# Group_1-1_PP.net
KiCad netlist of a schematic drawn in EAGLE
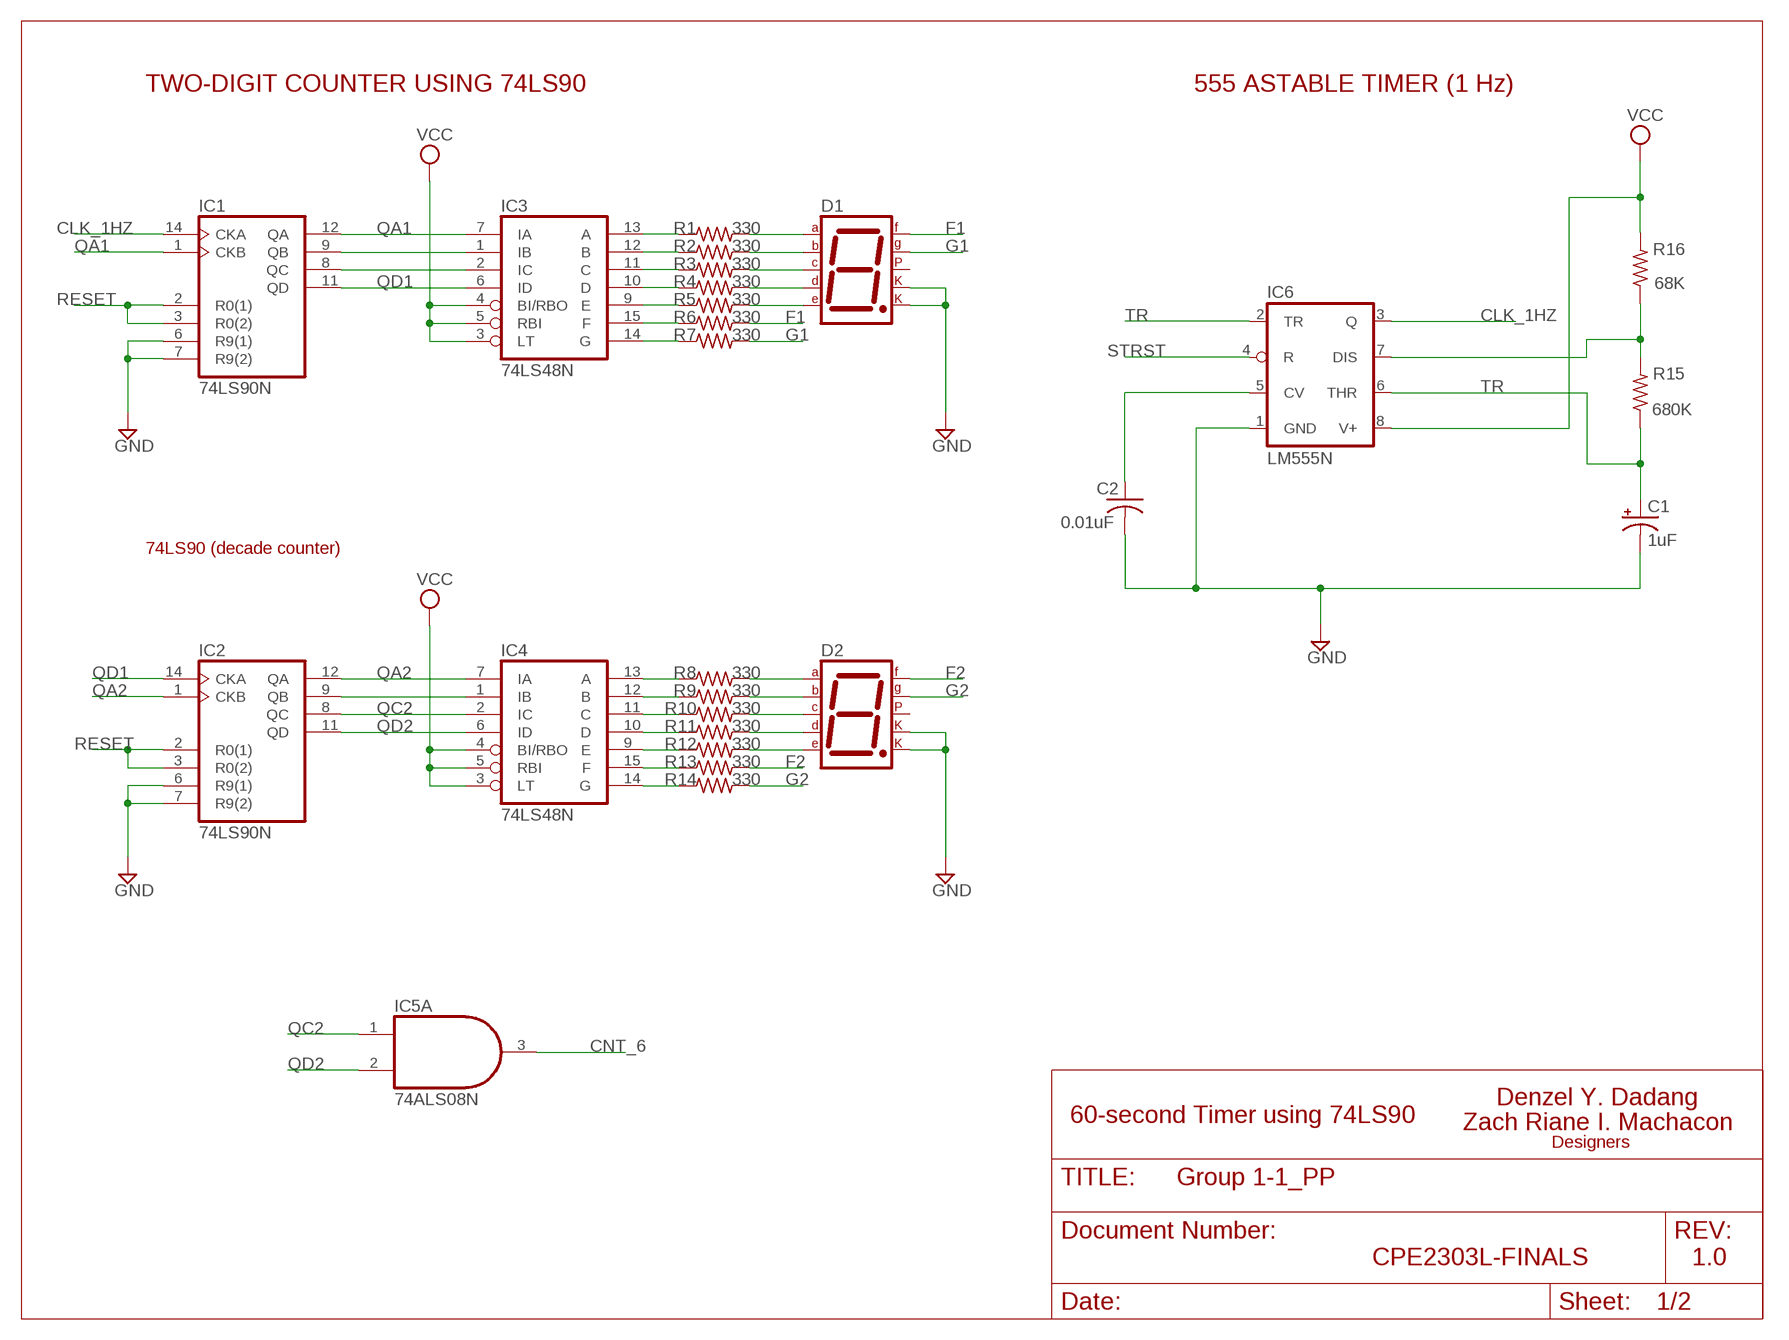
[diagram p0: schematic, sheet 1]
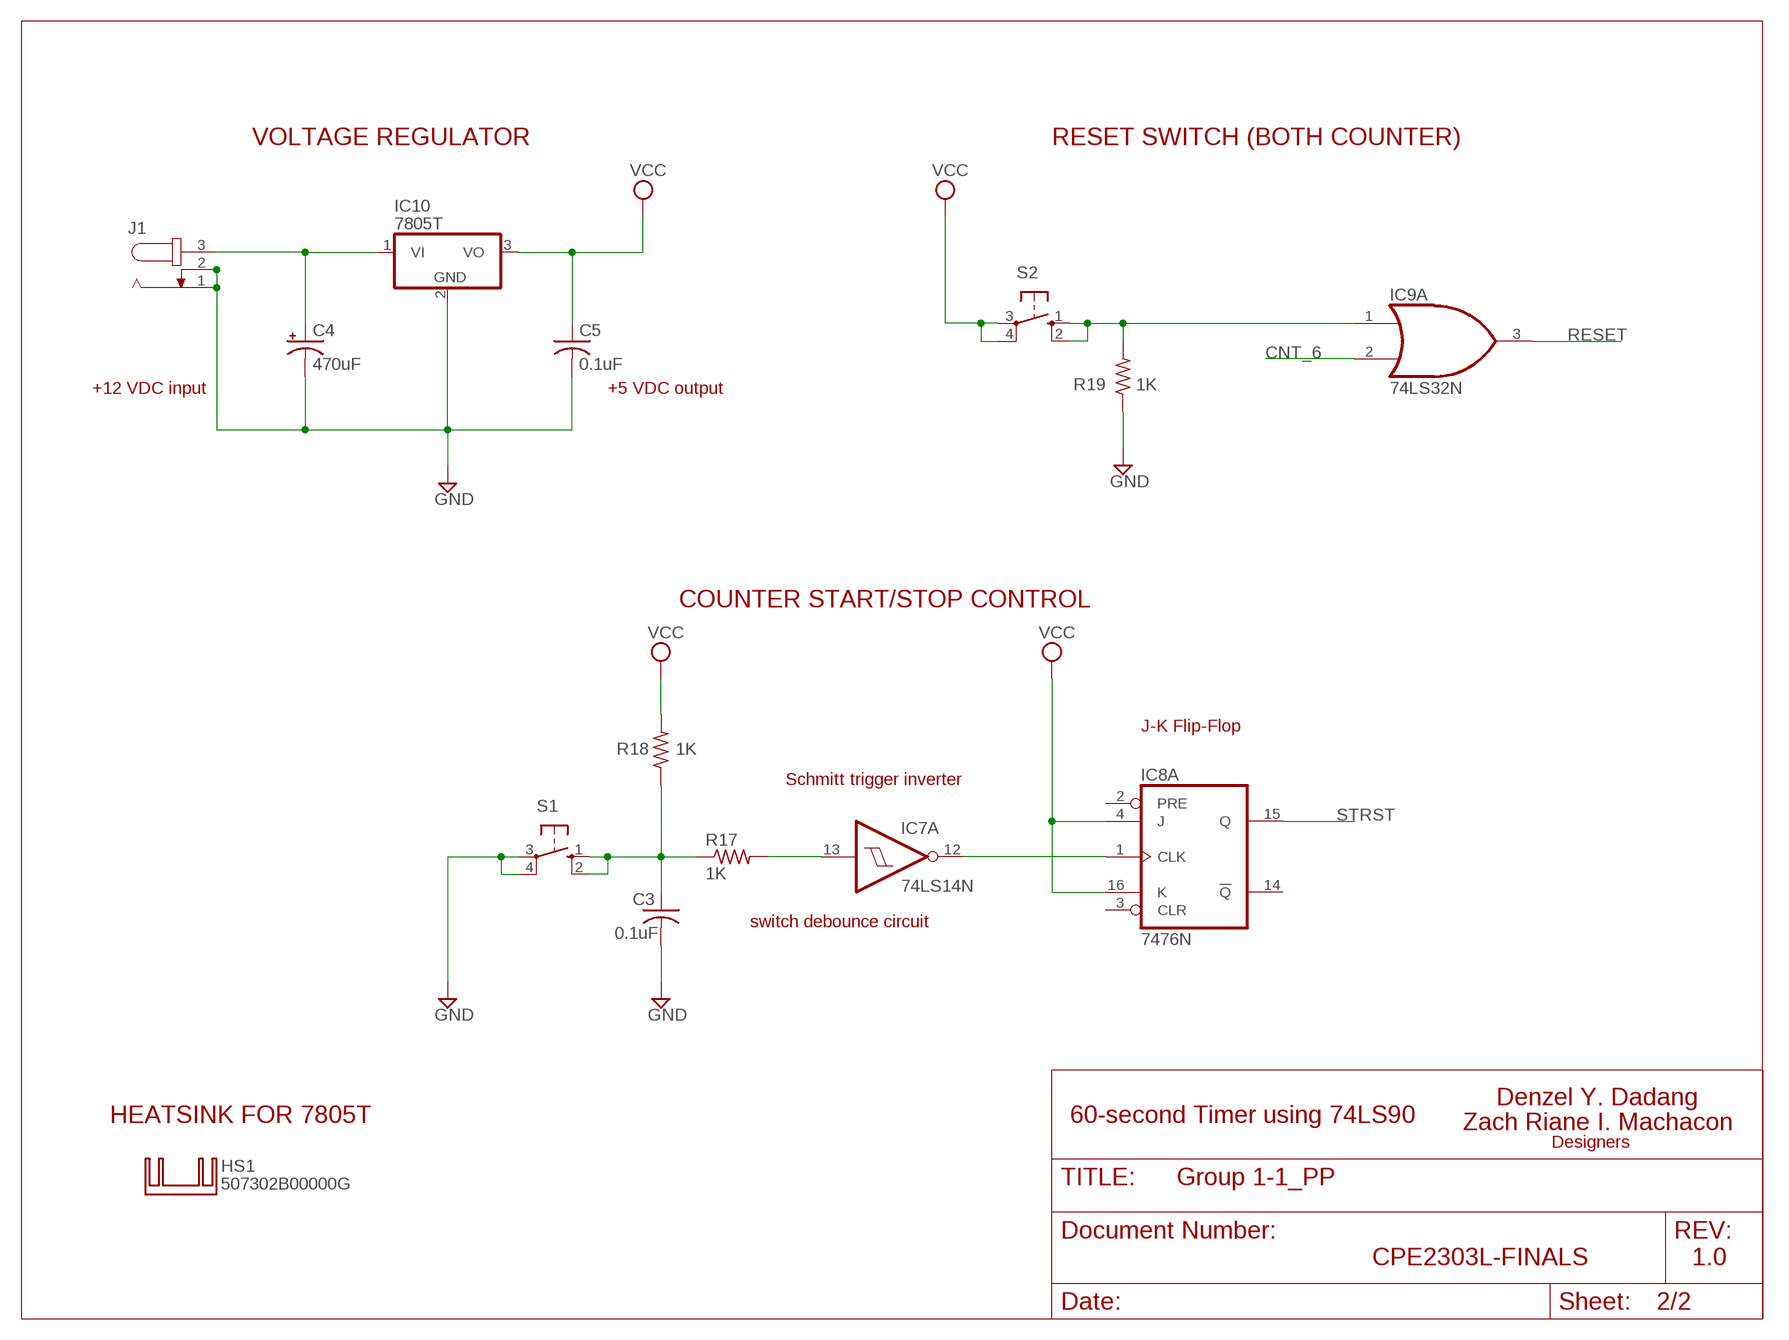
[diagram p1: schematic, sheet 2]

(export (version "E")
  (design (tool "Eeschema 10.0.6"))
  (components
    (comp (ref "C3")
      (value "0.1uF")
      (footprint "eagle-import:C025-025X050")
      (libsource (lib "eagle-import") (part "C-US025-025X050"))
    )
    (comp (ref "C4")
      (value "470uF")
      (footprint "eagle-import:E1,8-4")
      (libsource (lib "eagle-import") (part "CPOL-USE1.8-4"))
    )
    (comp (ref "C5")
      (value "0.1uF")
      (footprint "eagle-import:C025-025X050")
      (libsource (lib "eagle-import") (part "C-US025-025X050"))
    )
    (comp (ref "HS1")
      (value "507302B00000G")
      (footprint "eagle-import:TO-220H")
      (libsource (lib "eagle-import") (part "507302B00000G"))
    )
    (comp (ref "IC7")
      (value "74LS14N")
      (footprint "eagle-import:DIL14")
      (libsource (lib "eagle-import") (part "7414NLS"))
    )
    (comp (ref "IC8")
      (value "7476N")
      (footprint "eagle-import:DIL16")
      (libsource (lib "eagle-import") (part "7476N"))
    )
    (comp (ref "IC9")
      (value "74LS32N")
      (footprint "eagle-import:DIL14")
      (libsource (lib "eagle-import") (part "7432NLS"))
    )
    (comp (ref "IC10")
      (value "7805T")
      (footprint "eagle-import:TO220H")
      (libsource (lib "eagle-import") (part "78T05"))
    )
    (comp (ref "J1")
      (value "JACK-PLUG1")
      (footprint "eagle-import:SPC4078")
      (libsource (lib "eagle-import") (part "JACK-PLUG1"))
    )
    (comp (ref "R17")
      (value "1K")
      (footprint "eagle-import:0204_7")
      (libsource (lib "eagle-import") (part "R-US_0204/7"))
    )
    (comp (ref "R18")
      (value "1K")
      (footprint "eagle-import:0204_7")
      (libsource (lib "eagle-import") (part "R-US_0204/7"))
    )
    (comp (ref "R19")
      (value "1K")
      (footprint "eagle-import:0204_7")
      (libsource (lib "eagle-import") (part "R-US_0204/7"))
    )
    (comp (ref "S1")
      (value "10-XX")
      (footprint "eagle-import:B3F-10XX")
      (fields (field (name "MPN") "B3F-1000"))
      (libsource (lib "eagle-import") (part "10-XX"))
    )
    (comp (ref "S2")
      (value "10-XX")
      (footprint "eagle-import:B3F-10XX")
      (fields (field (name "MPN") "B3F-1000"))
      (libsource (lib "eagle-import") (part "10-XX"))
    )
    (comp (ref "C1")
      (value "1uF")
      (footprint "eagle-import:E1,8-4")
      (libsource (lib "eagle-import") (part "CPOL-USE1.8-4"))
    )
    (comp (ref "C2")
      (value "0.01uF")
      (footprint "eagle-import:C025-025X050")
      (libsource (lib "eagle-import") (part "C-US025-025X050"))
    )
    (comp (ref "D1")
      (value "7SEG-CK")
      (footprint "eagle-import:7SEG-13")
      (libsource (lib "eagle-import") (part "7SEG-CK"))
    )
    (comp (ref "D2")
      (value "7SEG-CK")
      (footprint "eagle-import:7SEG-13")
      (libsource (lib "eagle-import") (part "7SEG-CK"))
    )
    (comp (ref "IC1")
      (value "74LS90N")
      (footprint "eagle-import:DIL14")
      (libsource (lib "eagle-import") (part "7490NLS"))
    )
    (comp (ref "IC2")
      (value "74LS90N")
      (footprint "eagle-import:DIL14")
      (libsource (lib "eagle-import") (part "7490NLS"))
    )
    (comp (ref "IC3")
      (value "74LS48N")
      (footprint "eagle-import:DIL16")
      (libsource (lib "eagle-import") (part "7448NLS"))
    )
    (comp (ref "IC4")
      (value "74LS48N")
      (footprint "eagle-import:DIL16")
      (libsource (lib "eagle-import") (part "7448NLS"))
    )
    (comp (ref "IC5")
      (value "74ALS08N")
      (footprint "eagle-import:DIL14")
      (libsource (lib "eagle-import") (part "7408NALS"))
    )
    (comp (ref "IC6")
      (value "LM555N")
      (footprint "eagle-import:DIL08")
      (libsource (lib "eagle-import") (part "555NLM"))
    )
    (comp (ref "R1")
      (value "330")
      (footprint "eagle-import:0204_7")
      (libsource (lib "eagle-import") (part "R-US_0204/7"))
    )
    (comp (ref "R2")
      (value "330")
      (footprint "eagle-import:0204_7")
      (libsource (lib "eagle-import") (part "R-US_0204/7"))
    )
    (comp (ref "R3")
      (value "330")
      (footprint "eagle-import:0204_7")
      (libsource (lib "eagle-import") (part "R-US_0204/7"))
    )
    (comp (ref "R4")
      (value "330")
      (footprint "eagle-import:0204_7")
      (libsource (lib "eagle-import") (part "R-US_0204/7"))
    )
    (comp (ref "R5")
      (value "330")
      (footprint "eagle-import:0204_7")
      (libsource (lib "eagle-import") (part "R-US_0204/7"))
    )
    (comp (ref "R6")
      (value "330")
      (footprint "eagle-import:0204_7")
      (libsource (lib "eagle-import") (part "R-US_0204/7"))
    )
    (comp (ref "R7")
      (value "330")
      (footprint "eagle-import:0204_7")
      (libsource (lib "eagle-import") (part "R-US_0204/7"))
    )
    (comp (ref "R8")
      (value "330")
      (footprint "eagle-import:0204_7")
      (libsource (lib "eagle-import") (part "R-US_0204/7"))
    )
    (comp (ref "R9")
      (value "330")
      (footprint "eagle-import:0204_7")
      (libsource (lib "eagle-import") (part "R-US_0204/7"))
    )
    (comp (ref "R10")
      (value "330")
      (footprint "eagle-import:0204_7")
      (libsource (lib "eagle-import") (part "R-US_0204/7"))
    )
    (comp (ref "R11")
      (value "330")
      (footprint "eagle-import:0204_7")
      (libsource (lib "eagle-import") (part "R-US_0204/7"))
    )
    (comp (ref "R12")
      (value "330")
      (footprint "eagle-import:0204_7")
      (libsource (lib "eagle-import") (part "R-US_0204/7"))
    )
    (comp (ref "R13")
      (value "330")
      (footprint "eagle-import:0204_7")
      (libsource (lib "eagle-import") (part "R-US_0204/7"))
    )
    (comp (ref "R14")
      (value "330")
      (footprint "eagle-import:0204_7")
      (libsource (lib "eagle-import") (part "R-US_0204/7"))
    )
    (comp (ref "R15")
      (value "680K")
      (footprint "eagle-import:0204_7")
      (libsource (lib "eagle-import") (part "R-US_0204/7"))
    )
    (comp (ref "R16")
      (value "68K")
      (footprint "eagle-import:0204_7")
      (libsource (lib "eagle-import") (part "R-US_0204/7"))
    )
  )
  (nets
    (net (code "1") (name "CLK_1HZ") (class "Default")
      (node (ref "IC1") (pin "14") (pinfunction "CKA_14") (pintype "input"))
      (node (ref "IC6") (pin "3") (pinfunction "Q_3") (pintype "output"))
    )
    (net (code "2") (name "CNT_6") (class "Default")
      (node (ref "IC5") (pin "3") (pinfunction "O_3") (pintype "output"))
      (node (ref "IC9") (pin "2") (pinfunction "I1_2") (pintype "input"))
    )
    (net (code "3") (name "F1") (class "Default")
      (node (ref "D1") (pin "9") (pinfunction "F_9") (pintype "passive"))
      (node (ref "R6") (pin "2") (pinfunction "2_2") (pintype "passive"))
    )
    (net (code "4") (name "F2") (class "Default")
      (node (ref "D2") (pin "9") (pinfunction "F_9") (pintype "passive"))
      (node (ref "R13") (pin "2") (pinfunction "2_2") (pintype "passive"))
    )
    (net (code "5") (name "G1") (class "Default")
      (node (ref "D1") (pin "10") (pinfunction "G_10") (pintype "passive"))
      (node (ref "R7") (pin "2") (pinfunction "2_2") (pintype "passive"))
    )
    (net (code "6") (name "G2") (class "Default")
      (node (ref "D2") (pin "10") (pinfunction "G_10") (pintype "passive"))
      (node (ref "R14") (pin "2") (pinfunction "2_2") (pintype "passive"))
    )
    (net (code "7") (name "GND") (class "Default")
      (node (ref "C1") (pin "-") (pinfunction "-_-") (pintype "passive"))
      (node (ref "C2") (pin "2") (pinfunction "2_2") (pintype "passive"))
      (node (ref "C3") (pin "2") (pinfunction "2_2") (pintype "passive"))
      (node (ref "C4") (pin "-") (pinfunction "-_-") (pintype "passive"))
      (node (ref "C5") (pin "2") (pinfunction "2_2") (pintype "passive"))
      (node (ref "D1") (pin "3") (pinfunction "CK1_3") (pintype "passive"))
      (node (ref "D1") (pin "8") (pinfunction "CK2_8") (pintype "passive"))
      (node (ref "D2") (pin "3") (pinfunction "CK1_3") (pintype "passive"))
      (node (ref "D2") (pin "8") (pinfunction "CK2_8") (pintype "passive"))
      (node (ref "IC1") (pin "6") (pinfunction "R9(1)_6") (pintype "input"))
      (node (ref "IC1") (pin "7") (pinfunction "R9(2)_7") (pintype "input"))
      (node (ref "IC10") (pin "2") (pinfunction "GND_2") (pintype "passive"))
      (node (ref "IC2") (pin "6") (pinfunction "R9(1)_6") (pintype "input"))
      (node (ref "IC2") (pin "7") (pinfunction "R9(2)_7") (pintype "input"))
      (node (ref "IC6") (pin "1") (pinfunction "GND_1") (pintype "power_in"))
      (node (ref "J1") (pin "1") (pinfunction "1_1") (pintype "passive"))
      (node (ref "J1") (pin "2") (pinfunction "2_2") (pintype "passive"))
      (node (ref "R19") (pin "1") (pinfunction "1_1") (pintype "passive"))
      (node (ref "S1") (pin "3") (pinfunction "P_3") (pintype "passive"))
      (node (ref "S1") (pin "4") (pinfunction "P1_4") (pintype "passive"))
    )
    (net (code "8") (name "Net-(D1-A)") (class "Default")
      (node (ref "D1") (pin "7") (pinfunction "A_7") (pintype "passive"))
      (node (ref "R1") (pin "2") (pinfunction "2_2") (pintype "passive"))
    )
    (net (code "9") (name "Net-(D1-B)") (class "Default")
      (node (ref "D1") (pin "6") (pinfunction "B_6") (pintype "passive"))
      (node (ref "R2") (pin "2") (pinfunction "2_2") (pintype "passive"))
    )
    (net (code "10") (name "Net-(D1-C)") (class "Default")
      (node (ref "D1") (pin "4") (pinfunction "C_4") (pintype "passive"))
      (node (ref "R3") (pin "2") (pinfunction "2_2") (pintype "passive"))
    )
    (net (code "11") (name "Net-(D1-D)") (class "Default")
      (node (ref "D1") (pin "2") (pinfunction "D_2") (pintype "passive"))
      (node (ref "R4") (pin "2") (pinfunction "2_2") (pintype "passive"))
    )
    (net (code "12") (name "Net-(D1-E)") (class "Default")
      (node (ref "D1") (pin "1") (pinfunction "E_1") (pintype "passive"))
      (node (ref "R5") (pin "2") (pinfunction "2_2") (pintype "passive"))
    )
    (net (code "13") (name "Net-(D2-A)") (class "Default")
      (node (ref "D2") (pin "7") (pinfunction "A_7") (pintype "passive"))
      (node (ref "R8") (pin "2") (pinfunction "2_2") (pintype "passive"))
    )
    (net (code "14") (name "Net-(D2-B)") (class "Default")
      (node (ref "D2") (pin "6") (pinfunction "B_6") (pintype "passive"))
      (node (ref "R9") (pin "2") (pinfunction "2_2") (pintype "passive"))
    )
    (net (code "15") (name "Net-(D2-C)") (class "Default")
      (node (ref "D2") (pin "4") (pinfunction "C_4") (pintype "passive"))
      (node (ref "R10") (pin "2") (pinfunction "2_2") (pintype "passive"))
    )
    (net (code "16") (name "Net-(D2-D)") (class "Default")
      (node (ref "D2") (pin "2") (pinfunction "D_2") (pintype "passive"))
      (node (ref "R11") (pin "2") (pinfunction "2_2") (pintype "passive"))
    )
    (net (code "17") (name "Net-(D2-E)") (class "Default")
      (node (ref "D2") (pin "1") (pinfunction "E_1") (pintype "passive"))
      (node (ref "R12") (pin "2") (pinfunction "2_2") (pintype "passive"))
    )
    (net (code "18") (name "Net-(IC1A-QB)") (class "Default")
      (node (ref "IC1") (pin "9") (pinfunction "QB_9") (pintype "output"))
      (node (ref "IC3") (pin "1") (pinfunction "IB_1") (pintype "input"))
    )
    (net (code "19") (name "Net-(IC1A-QC)") (class "Default")
      (node (ref "IC1") (pin "8") (pinfunction "QC_8") (pintype "output"))
      (node (ref "IC3") (pin "2") (pinfunction "IC_2") (pintype "input"))
    )
    (net (code "20") (name "Net-(IC2A-QB)") (class "Default")
      (node (ref "IC2") (pin "9") (pinfunction "QB_9") (pintype "output"))
      (node (ref "IC4") (pin "1") (pinfunction "IB_1") (pintype "input"))
    )
    (net (code "21") (name "Net-(IC3A-A)") (class "Default")
      (node (ref "IC3") (pin "13") (pinfunction "A_13") (pintype "output"))
      (node (ref "R1") (pin "1") (pinfunction "1_1") (pintype "passive"))
    )
    (net (code "22") (name "Net-(IC3A-B)") (class "Default")
      (node (ref "IC3") (pin "12") (pinfunction "B_12") (pintype "output"))
      (node (ref "R2") (pin "1") (pinfunction "1_1") (pintype "passive"))
    )
    (net (code "23") (name "Net-(IC3A-C)") (class "Default")
      (node (ref "IC3") (pin "11") (pinfunction "C_11") (pintype "output"))
      (node (ref "R3") (pin "1") (pinfunction "1_1") (pintype "passive"))
    )
    (net (code "24") (name "Net-(IC3A-D)") (class "Default")
      (node (ref "IC3") (pin "10") (pinfunction "D_10") (pintype "output"))
      (node (ref "R4") (pin "1") (pinfunction "1_1") (pintype "passive"))
    )
    (net (code "25") (name "Net-(IC3A-E)") (class "Default")
      (node (ref "IC3") (pin "9") (pinfunction "E_9") (pintype "output"))
      (node (ref "R5") (pin "1") (pinfunction "1_1") (pintype "passive"))
    )
    (net (code "26") (name "Net-(IC3A-F)") (class "Default")
      (node (ref "IC3") (pin "15") (pinfunction "F_15") (pintype "output"))
      (node (ref "R6") (pin "1") (pinfunction "1_1") (pintype "passive"))
    )
    (net (code "27") (name "Net-(IC3A-G)") (class "Default")
      (node (ref "IC3") (pin "14") (pinfunction "G_14") (pintype "output"))
      (node (ref "R7") (pin "1") (pinfunction "1_1") (pintype "passive"))
    )
    (net (code "28") (name "Net-(IC4A-A)") (class "Default")
      (node (ref "IC4") (pin "13") (pinfunction "A_13") (pintype "output"))
      (node (ref "R8") (pin "1") (pinfunction "1_1") (pintype "passive"))
    )
    (net (code "29") (name "Net-(IC4A-B)") (class "Default")
      (node (ref "IC4") (pin "12") (pinfunction "B_12") (pintype "output"))
      (node (ref "R9") (pin "1") (pinfunction "1_1") (pintype "passive"))
    )
    (net (code "30") (name "Net-(IC4A-C)") (class "Default")
      (node (ref "IC4") (pin "11") (pinfunction "C_11") (pintype "output"))
      (node (ref "R10") (pin "1") (pinfunction "1_1") (pintype "passive"))
    )
    (net (code "31") (name "Net-(IC4A-D)") (class "Default")
      (node (ref "IC4") (pin "10") (pinfunction "D_10") (pintype "output"))
      (node (ref "R11") (pin "1") (pinfunction "1_1") (pintype "passive"))
    )
    (net (code "32") (name "Net-(IC4A-E)") (class "Default")
      (node (ref "IC4") (pin "9") (pinfunction "E_9") (pintype "output"))
      (node (ref "R12") (pin "1") (pinfunction "1_1") (pintype "passive"))
    )
    (net (code "33") (name "Net-(IC4A-F)") (class "Default")
      (node (ref "IC4") (pin "15") (pinfunction "F_15") (pintype "output"))
      (node (ref "R13") (pin "1") (pinfunction "1_1") (pintype "passive"))
    )
    (net (code "34") (name "Net-(IC4A-G)") (class "Default")
      (node (ref "IC4") (pin "14") (pinfunction "G_14") (pintype "output"))
      (node (ref "R14") (pin "1") (pinfunction "1_1") (pintype "passive"))
    )
    (net (code "35") (name "Net-(IC6-CV)") (class "Default")
      (node (ref "C2") (pin "1") (pinfunction "1_1") (pintype "passive"))
      (node (ref "IC6") (pin "5") (pinfunction "CV_5") (pintype "input"))
    )
    (net (code "36") (name "Net-(IC6-DIS)") (class "Default")
      (node (ref "IC6") (pin "7") (pinfunction "DIS_7") (pintype "input"))
      (node (ref "R15") (pin "2") (pinfunction "2_2") (pintype "passive"))
      (node (ref "R16") (pin "1") (pinfunction "1_1") (pintype "passive"))
    )
    (net (code "37") (name "Net-(IC7A-I)") (class "Default")
      (node (ref "IC7") (pin "13") (pinfunction "I_13") (pintype "input"))
      (node (ref "R17") (pin "2") (pinfunction "2_2") (pintype "passive"))
    )
    (net (code "38") (name "Net-(IC7A-O)") (class "Default")
      (node (ref "IC7") (pin "12") (pinfunction "O_12") (pintype "output"))
      (node (ref "IC8") (pin "1") (pinfunction "CLK_1") (pintype "input"))
    )
    (net (code "39") (name "Net-(IC9A-I0)") (class "Default")
      (node (ref "IC9") (pin "1") (pinfunction "I0_1") (pintype "input"))
      (node (ref "R19") (pin "2") (pinfunction "2_2") (pintype "passive"))
      (node (ref "S2") (pin "1") (pinfunction "S_1") (pintype "passive"))
      (node (ref "S2") (pin "2") (pinfunction "S1_2") (pintype "passive"))
    )
    (net (code "40") (name "Net-(IC10-VI)") (class "Default")
      (node (ref "C4") (pin "+") (pinfunction "+_+") (pintype "passive"))
      (node (ref "IC10") (pin "1") (pinfunction "VI_1") (pintype "input"))
      (node (ref "J1") (pin "3") (pinfunction "3_3") (pintype "passive"))
    )
    (net (code "41") (name "Net-(S1-S)") (class "Default")
      (node (ref "C3") (pin "1") (pinfunction "1_1") (pintype "passive"))
      (node (ref "R17") (pin "1") (pinfunction "1_1") (pintype "passive"))
      (node (ref "R18") (pin "1") (pinfunction "1_1") (pintype "passive"))
      (node (ref "S1") (pin "1") (pinfunction "S_1") (pintype "passive"))
      (node (ref "S1") (pin "2") (pinfunction "S1_2") (pintype "passive"))
    )
    (net (code "42") (name "QA1") (class "Default")
      (node (ref "IC1") (pin "1") (pinfunction "CKB_1") (pintype "input"))
      (node (ref "IC1") (pin "12") (pinfunction "QA_12") (pintype "output"))
      (node (ref "IC3") (pin "7") (pinfunction "IA_7") (pintype "input"))
    )
    (net (code "43") (name "QA2") (class "Default")
      (node (ref "IC2") (pin "1") (pinfunction "CKB_1") (pintype "input"))
      (node (ref "IC2") (pin "12") (pinfunction "QA_12") (pintype "output"))
      (node (ref "IC4") (pin "7") (pinfunction "IA_7") (pintype "input"))
    )
    (net (code "44") (name "QC2") (class "Default")
      (node (ref "IC2") (pin "8") (pinfunction "QC_8") (pintype "output"))
      (node (ref "IC4") (pin "2") (pinfunction "IC_2") (pintype "input"))
      (node (ref "IC5") (pin "1") (pinfunction "I0_1") (pintype "input"))
    )
    (net (code "45") (name "QD1") (class "Default")
      (node (ref "IC1") (pin "11") (pinfunction "QD_11") (pintype "output"))
      (node (ref "IC2") (pin "14") (pinfunction "CKA_14") (pintype "input"))
      (node (ref "IC3") (pin "6") (pinfunction "ID_6") (pintype "input"))
    )
    (net (code "46") (name "QD2") (class "Default")
      (node (ref "IC2") (pin "11") (pinfunction "QD_11") (pintype "output"))
      (node (ref "IC4") (pin "6") (pinfunction "ID_6") (pintype "input"))
      (node (ref "IC5") (pin "2") (pinfunction "I1_2") (pintype "input"))
    )
    (net (code "47") (name "RESET") (class "Default")
      (node (ref "IC1") (pin "2") (pinfunction "R0(1)_2") (pintype "input"))
      (node (ref "IC1") (pin "3") (pinfunction "R0(2)_3") (pintype "input"))
      (node (ref "IC2") (pin "2") (pinfunction "R0(1)_2") (pintype "input"))
      (node (ref "IC2") (pin "3") (pinfunction "R0(2)_3") (pintype "input"))
      (node (ref "IC9") (pin "3") (pinfunction "O_3") (pintype "output"))
    )
    (net (code "48") (name "STRST") (class "Default")
      (node (ref "IC6") (pin "4") (pinfunction "R_4") (pintype "input"))
      (node (ref "IC8") (pin "15") (pinfunction "Q_15") (pintype "output"))
    )
    (net (code "49") (name "TR") (class "Default")
      (node (ref "C1") (pin "+") (pinfunction "+_+") (pintype "passive"))
      (node (ref "IC6") (pin "2") (pinfunction "TR_2") (pintype "input"))
      (node (ref "IC6") (pin "6") (pinfunction "THR_6") (pintype "input"))
      (node (ref "R15") (pin "1") (pinfunction "1_1") (pintype "passive"))
    )
    (net (code "50") (name "VCC") (class "Default")
      (node (ref "C5") (pin "1") (pinfunction "1_1") (pintype "passive"))
      (node (ref "IC10") (pin "3") (pinfunction "VO_3") (pintype "passive"))
      (node (ref "IC3") (pin "3") (pinfunction "LT_3") (pintype "input"))
      (node (ref "IC3") (pin "4") (pinfunction "BI/RBO_4") (pintype "input"))
      (node (ref "IC3") (pin "5") (pinfunction "RBI_5") (pintype "input"))
      (node (ref "IC4") (pin "3") (pinfunction "LT_3") (pintype "input"))
      (node (ref "IC4") (pin "4") (pinfunction "BI/RBO_4") (pintype "input"))
      (node (ref "IC4") (pin "5") (pinfunction "RBI_5") (pintype "input"))
      (node (ref "IC6") (pin "8") (pinfunction "V+_8") (pintype "power_in"))
      (node (ref "IC8") (pin "16") (pinfunction "K_16") (pintype "input"))
      (node (ref "IC8") (pin "4") (pinfunction "J_4") (pintype "input"))
      (node (ref "R16") (pin "2") (pinfunction "2_2") (pintype "passive"))
      (node (ref "R18") (pin "2") (pinfunction "2_2") (pintype "passive"))
      (node (ref "S2") (pin "3") (pinfunction "P_3") (pintype "passive"))
      (node (ref "S2") (pin "4") (pinfunction "P1_4") (pintype "passive"))
    )
    (net (code "51") (name "unconnected-(D1-DP-Pad5)") (class "Default")
      (node (ref "D1") (pin "5") (pinfunction "DP_5") (pintype "passive"))
    )
    (net (code "52") (name "unconnected-(D2-DP-Pad5)") (class "Default")
      (node (ref "D2") (pin "5") (pinfunction "DP_5") (pintype "passive"))
    )
    (net (code "53") (name "unconnected-(IC8A-CLR-Pad3)") (class "Default")
      (node (ref "IC8") (pin "3") (pinfunction "CLR_3") (pintype "input"))
    )
    (net (code "54") (name "unconnected-(IC8A-PRE-Pad2)") (class "Default")
      (node (ref "IC8") (pin "2") (pinfunction "PRE_2") (pintype "input"))
    )
    (net (code "55") (name "unconnected-(IC8A-~{Q}-Pad14)") (class "Default")
      (node (ref "IC8") (pin "14") (pinfunction "~{Q}_14") (pintype "output"))
    )
  )
)
